# Module_PowerSource.net
KiCad netlist of a schematic drawn in EAGLE
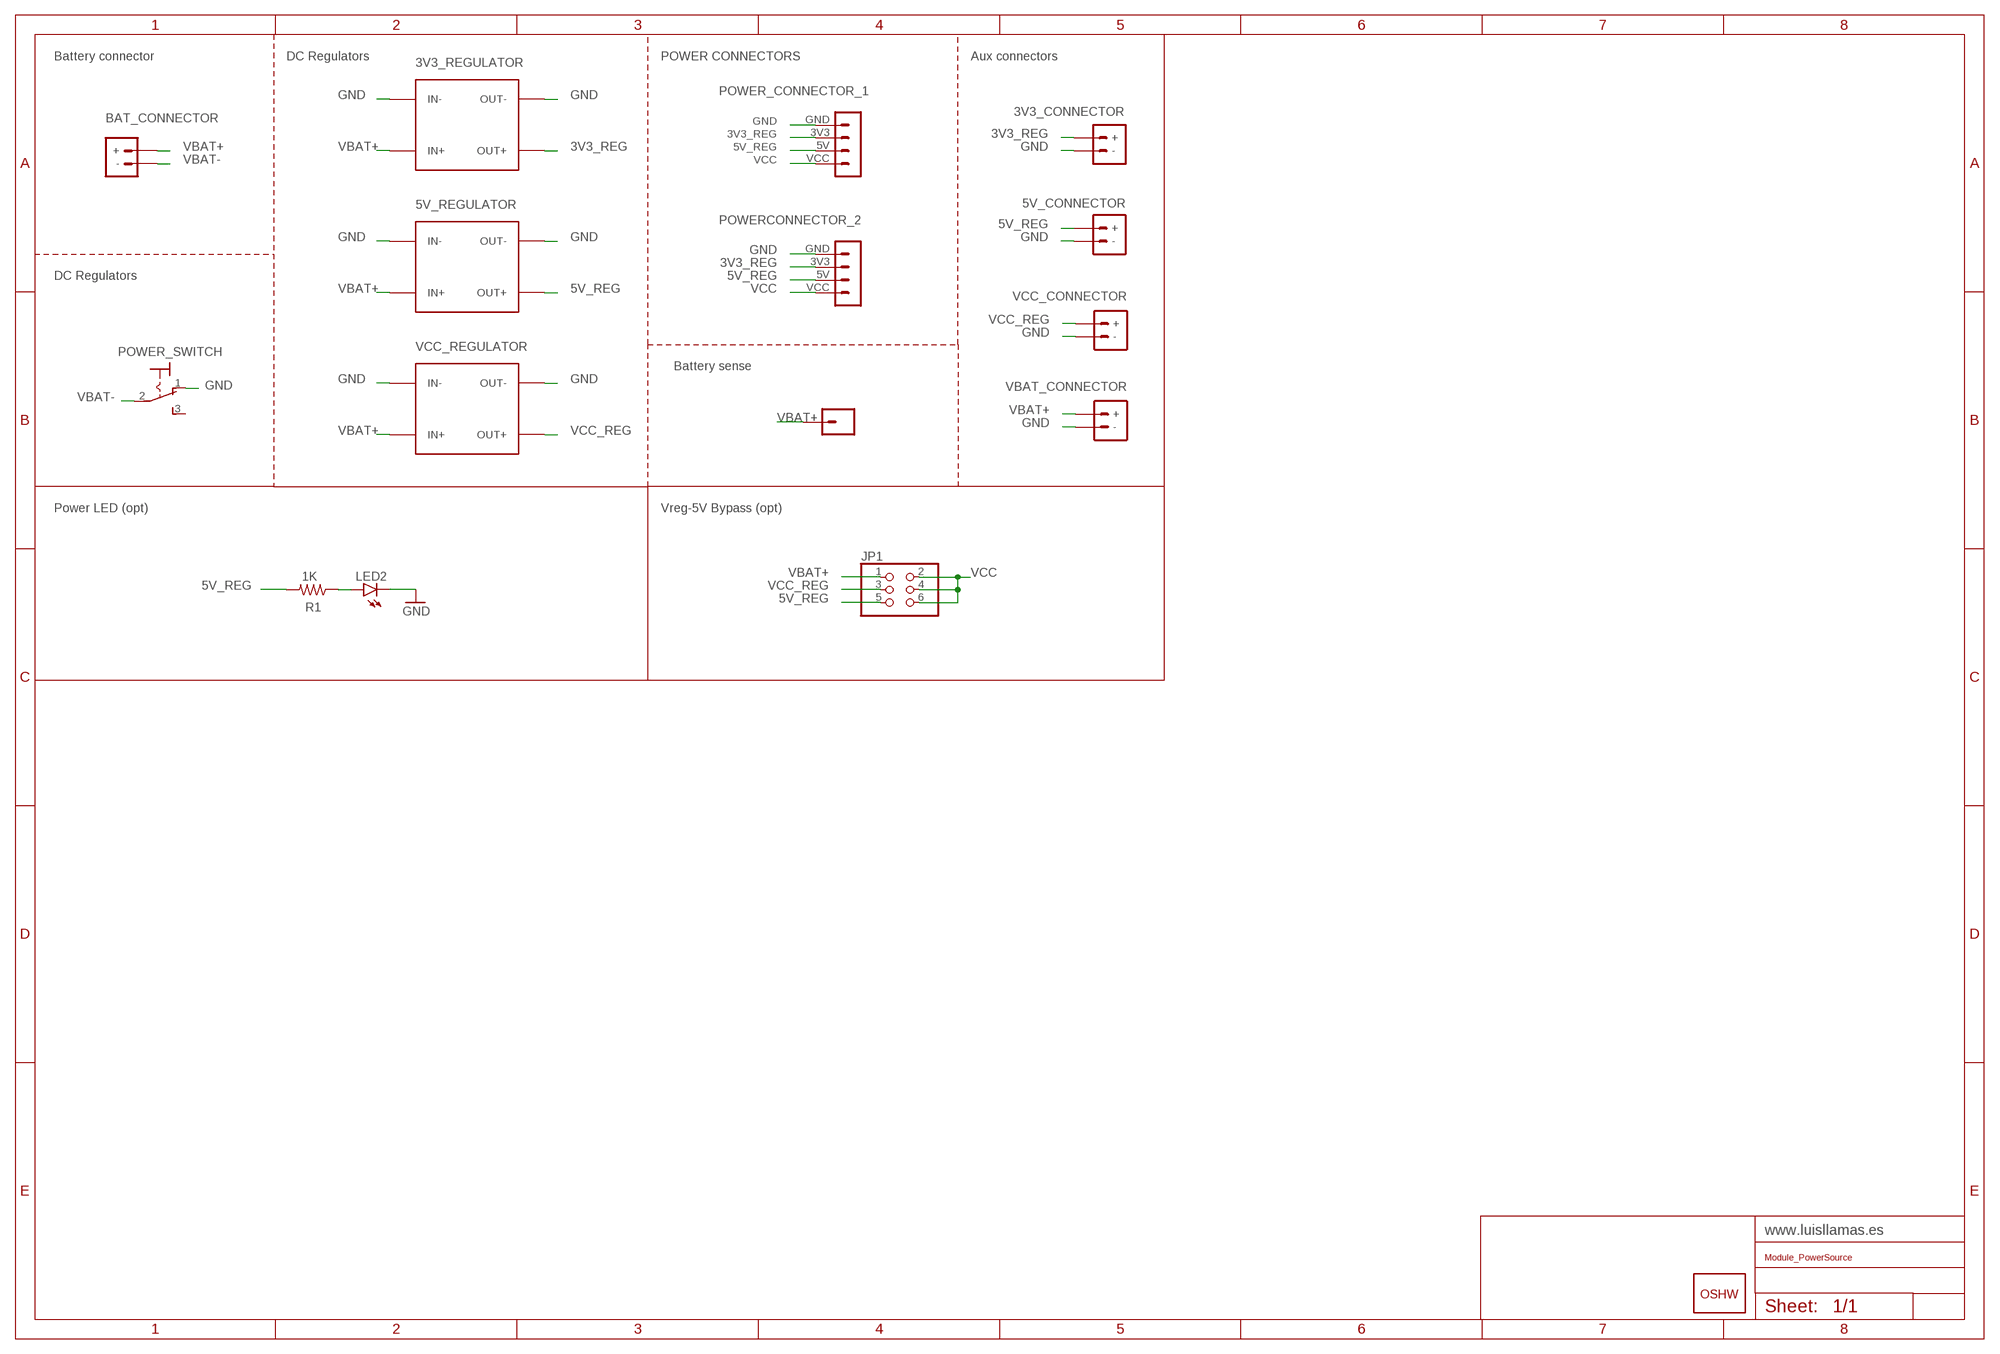
[diagram p0: schematic, sheet 1]

(export (version "E")
  (design (tool "Eeschema 10.0.6"))
  (components
    (comp (ref "3V3_CONNECTOR")
      (value "MOTOR-TERMINAL2.54MM_SCREWTERM")
      (footprint "eagle-import:1X02_2.54_SCREWTERM")
      (libsource (lib "eagle-import") (part "MOTOR-TERMINAL2.54MM_SCREWTERM"))
    )
    (comp (ref "3V3_REGULATOR")
      (value "MINI-DC-STEP-DOWN-MP2307")
      (footprint "eagle-import:MINI-DC-STEP-DOWN-MP2307")
      (libsource (lib "eagle-import") (part "MINI-DC-STEP-DOWN-MP2307"))
    )
    (comp (ref "5V_CONNECTOR")
      (value "MOTOR-TERMINAL2.54MM_SCREWTERM")
      (footprint "eagle-import:1X02_2.54_SCREWTERM")
      (libsource (lib "eagle-import") (part "MOTOR-TERMINAL2.54MM_SCREWTERM"))
    )
    (comp (ref "5V_REGULATOR")
      (value "MINI-DC-STEP-DOWN-MP2307")
      (footprint "eagle-import:MINI-DC-STEP-DOWN-MP2307")
      (libsource (lib "eagle-import") (part "MINI-DC-STEP-DOWN-MP2307"))
    )
    (comp (ref "BAT_CONNECTOR")
      (value "POWER-TERMINAL5MM")
      (footprint "eagle-import:SCREWTERMINAL-5MM-2")
      (libsource (lib "eagle-import") (part "POWER-TERMINAL5MM"))
    )
    (comp (ref "GOLD_ORB_SM1")
      (value "OSHWLOGO_GOLD_ORB_MED")
      (footprint "eagle-import:OSHW1")
      (libsource (lib "eagle-import") (part "OSHWLOGO_GOLD_ORB_MED"))
    )
    (comp (ref "J3")
      (value "CONN_01")
      (footprint "eagle-import:1X01")
      (libsource (lib "eagle-import") (part "CONN_01"))
    )
    (comp (ref "JP1")
      (value "JUMPER_3X2/OCT")
      (footprint "eagle-import:JUMPER_3X2")
      (libsource (lib "eagle-import") (part "JUMPER_3X2/OCT"))
    )
    (comp (ref "LED2")
      (value "LEDCHIP-LED0805")
      (footprint "eagle-import:CHIP-LED0805")
      (libsource (lib "eagle-import") (part "LEDCHIP-LED0805"))
    )
    (comp (ref "POWERCONNECTOR_2")
      (value "POWER-CONNECTOR")
      (footprint "eagle-import:POWER-CONNECTOR")
      (libsource (lib "eagle-import") (part "POWER-CONNECTOR"))
    )
    (comp (ref "POWER_CONNECTOR_1")
      (value "POWER-CONNECTOR")
      (footprint "eagle-import:POWER-CONNECTOR")
      (libsource (lib "eagle-import") (part "POWER-CONNECTOR"))
    )
    (comp (ref "POWER_SWITCH")
      (value "LEVER-POWER-SWITCH")
      (footprint "eagle-import:LEVER-POWER-SWITCH")
      (libsource (lib "eagle-import") (part "LEVER-POWER-SWITCH"))
    )
    (comp (ref "R1")
      (value "1K")
      (footprint "eagle-import:R0805")
      (libsource (lib "eagle-import") (part "R-US_R0805"))
    )
    (comp (ref "VBAT_CONNECTOR")
      (value "MOTOR-TERMINAL2.54MM_SCREWTERM")
      (footprint "eagle-import:1X02_2.54_SCREWTERM")
      (libsource (lib "eagle-import") (part "MOTOR-TERMINAL2.54MM_SCREWTERM"))
    )
    (comp (ref "VCC_CONNECTOR")
      (value "MOTOR-TERMINAL2.54MM_SCREWTERM")
      (footprint "eagle-import:1X02_2.54_SCREWTERM")
      (libsource (lib "eagle-import") (part "MOTOR-TERMINAL2.54MM_SCREWTERM"))
    )
    (comp (ref "VCC_REGULATOR")
      (value "MINI-DC-STEP-DOWN-MP2307")
      (footprint "eagle-import:MINI-DC-STEP-DOWN-MP2307")
      (libsource (lib "eagle-import") (part "MINI-DC-STEP-DOWN-MP2307"))
    )
  )
  (nets
    (net (code "1") (name "/3V3_REG") (class "Default")
      (node (ref "3V3_CONNECTOR") (pin "+") (pinfunction "+_+") (pintype "passive"))
      (node (ref "3V3_REGULATOR") (pin "OUT+") (pinfunction "OUT+_OUT+") (pintype "bidirectional"))
      (node (ref "3V3_REGULATOR") (pin "OUT2.+") (pinfunction "OUT+_OUT2.+") (pintype "bidirectional"))
      (node (ref "POWERCONNECTOR_2") (pin "3V3") (pinfunction "3V3_3V3") (pintype "passive"))
      (node (ref "POWER_CONNECTOR_1") (pin "3V3") (pinfunction "3V3_3V3") (pintype "passive"))
    )
    (net (code "2") (name "/5V_REG") (class "Default")
      (node (ref "5V_CONNECTOR") (pin "+") (pinfunction "+_+") (pintype "passive"))
      (node (ref "5V_REGULATOR") (pin "OUT+") (pinfunction "OUT+_OUT+") (pintype "bidirectional"))
      (node (ref "5V_REGULATOR") (pin "OUT2.+") (pinfunction "OUT+_OUT2.+") (pintype "bidirectional"))
      (node (ref "JP1") (pin "5") (pinfunction "5_5") (pintype "passive"))
      (node (ref "POWERCONNECTOR_2") (pin "5V") (pinfunction "5V_5V") (pintype "passive"))
      (node (ref "POWER_CONNECTOR_1") (pin "5V") (pinfunction "5V_5V") (pintype "passive"))
      (node (ref "R1") (pin "2") (pinfunction "2_2") (pintype "passive"))
    )
    (net (code "3") (name "/VBAT+") (class "Default")
      (node (ref "3V3_REGULATOR") (pin "IN+") (pinfunction "IN+_IN+") (pintype "bidirectional"))
      (node (ref "3V3_REGULATOR") (pin "IN.2+") (pinfunction "IN+_IN.2+") (pintype "bidirectional"))
      (node (ref "5V_REGULATOR") (pin "IN+") (pinfunction "IN+_IN+") (pintype "bidirectional"))
      (node (ref "5V_REGULATOR") (pin "IN.2+") (pinfunction "IN+_IN.2+") (pintype "bidirectional"))
      (node (ref "BAT_CONNECTOR") (pin "+") (pinfunction "+_+") (pintype "passive"))
      (node (ref "J3") (pin "1") (pinfunction "1_1") (pintype "passive"))
      (node (ref "JP1") (pin "1") (pinfunction "1_1") (pintype "passive"))
      (node (ref "VBAT_CONNECTOR") (pin "+") (pinfunction "+_+") (pintype "passive"))
      (node (ref "VCC_REGULATOR") (pin "IN+") (pinfunction "IN+_IN+") (pintype "bidirectional"))
      (node (ref "VCC_REGULATOR") (pin "IN.2+") (pinfunction "IN+_IN.2+") (pintype "bidirectional"))
    )
    (net (code "4") (name "/VBAT-") (class "Default")
      (node (ref "BAT_CONNECTOR") (pin "-") (pinfunction "-_-") (pintype "passive"))
      (node (ref "POWER_SWITCH") (pin "2") (pinfunction "P_2") (pintype "passive"))
    )
    (net (code "5") (name "/VCC") (class "Default")
      (node (ref "JP1") (pin "2") (pinfunction "2_2") (pintype "passive"))
      (node (ref "JP1") (pin "4") (pinfunction "4_4") (pintype "passive"))
      (node (ref "JP1") (pin "6") (pinfunction "6_6") (pintype "passive"))
      (node (ref "POWERCONNECTOR_2") (pin "VCC") (pinfunction "VCC_VCC") (pintype "passive"))
      (node (ref "POWER_CONNECTOR_1") (pin "VCC") (pinfunction "VCC_VCC") (pintype "passive"))
    )
    (net (code "6") (name "/VCC_REG") (class "Default")
      (node (ref "JP1") (pin "3") (pinfunction "3_3") (pintype "passive"))
      (node (ref "VCC_CONNECTOR") (pin "+") (pinfunction "+_+") (pintype "passive"))
      (node (ref "VCC_REGULATOR") (pin "OUT+") (pinfunction "OUT+_OUT+") (pintype "bidirectional"))
      (node (ref "VCC_REGULATOR") (pin "OUT2.+") (pinfunction "OUT+_OUT2.+") (pintype "bidirectional"))
    )
    (net (code "7") (name "GND") (class "Default")
      (node (ref "3V3_CONNECTOR") (pin "-") (pinfunction "-_-") (pintype "passive"))
      (node (ref "3V3_REGULATOR") (pin "IN-") (pinfunction "IN-_IN-") (pintype "bidirectional"))
      (node (ref "3V3_REGULATOR") (pin "OUT-") (pinfunction "OUT-_OUT-") (pintype "bidirectional"))
      (node (ref "5V_CONNECTOR") (pin "-") (pinfunction "-_-") (pintype "passive"))
      (node (ref "5V_REGULATOR") (pin "IN-") (pinfunction "IN-_IN-") (pintype "bidirectional"))
      (node (ref "5V_REGULATOR") (pin "OUT-") (pinfunction "OUT-_OUT-") (pintype "bidirectional"))
      (node (ref "LED2") (pin "C") (pinfunction "C_C") (pintype "passive"))
      (node (ref "POWERCONNECTOR_2") (pin "GND") (pinfunction "GND_GND") (pintype "passive"))
      (node (ref "POWER_CONNECTOR_1") (pin "GND") (pinfunction "GND_GND") (pintype "passive"))
      (node (ref "POWER_SWITCH") (pin "1") (pinfunction "O_1") (pintype "passive"))
      (node (ref "VBAT_CONNECTOR") (pin "-") (pinfunction "-_-") (pintype "passive"))
      (node (ref "VCC_CONNECTOR") (pin "-") (pinfunction "-_-") (pintype "passive"))
      (node (ref "VCC_REGULATOR") (pin "IN-") (pinfunction "IN-_IN-") (pintype "bidirectional"))
      (node (ref "VCC_REGULATOR") (pin "OUT-") (pinfunction "OUT-_OUT-") (pintype "bidirectional"))
    )
    (net (code "8") (name "Net-(LED2-PadA)") (class "Default")
      (node (ref "LED2") (pin "A") (pinfunction "A_A") (pintype "passive"))
      (node (ref "R1") (pin "1") (pinfunction "1_1") (pintype "passive"))
    )
    (net (code "9") (name "unconnected-(POWER_SWITCH-S-Pad3)") (class "Default")
      (node (ref "POWER_SWITCH") (pin "3") (pinfunction "S_3") (pintype "passive"))
    )
  )
)
